# Sheet5.net
KiCad netlist of a schematic drawn in Altium Designer
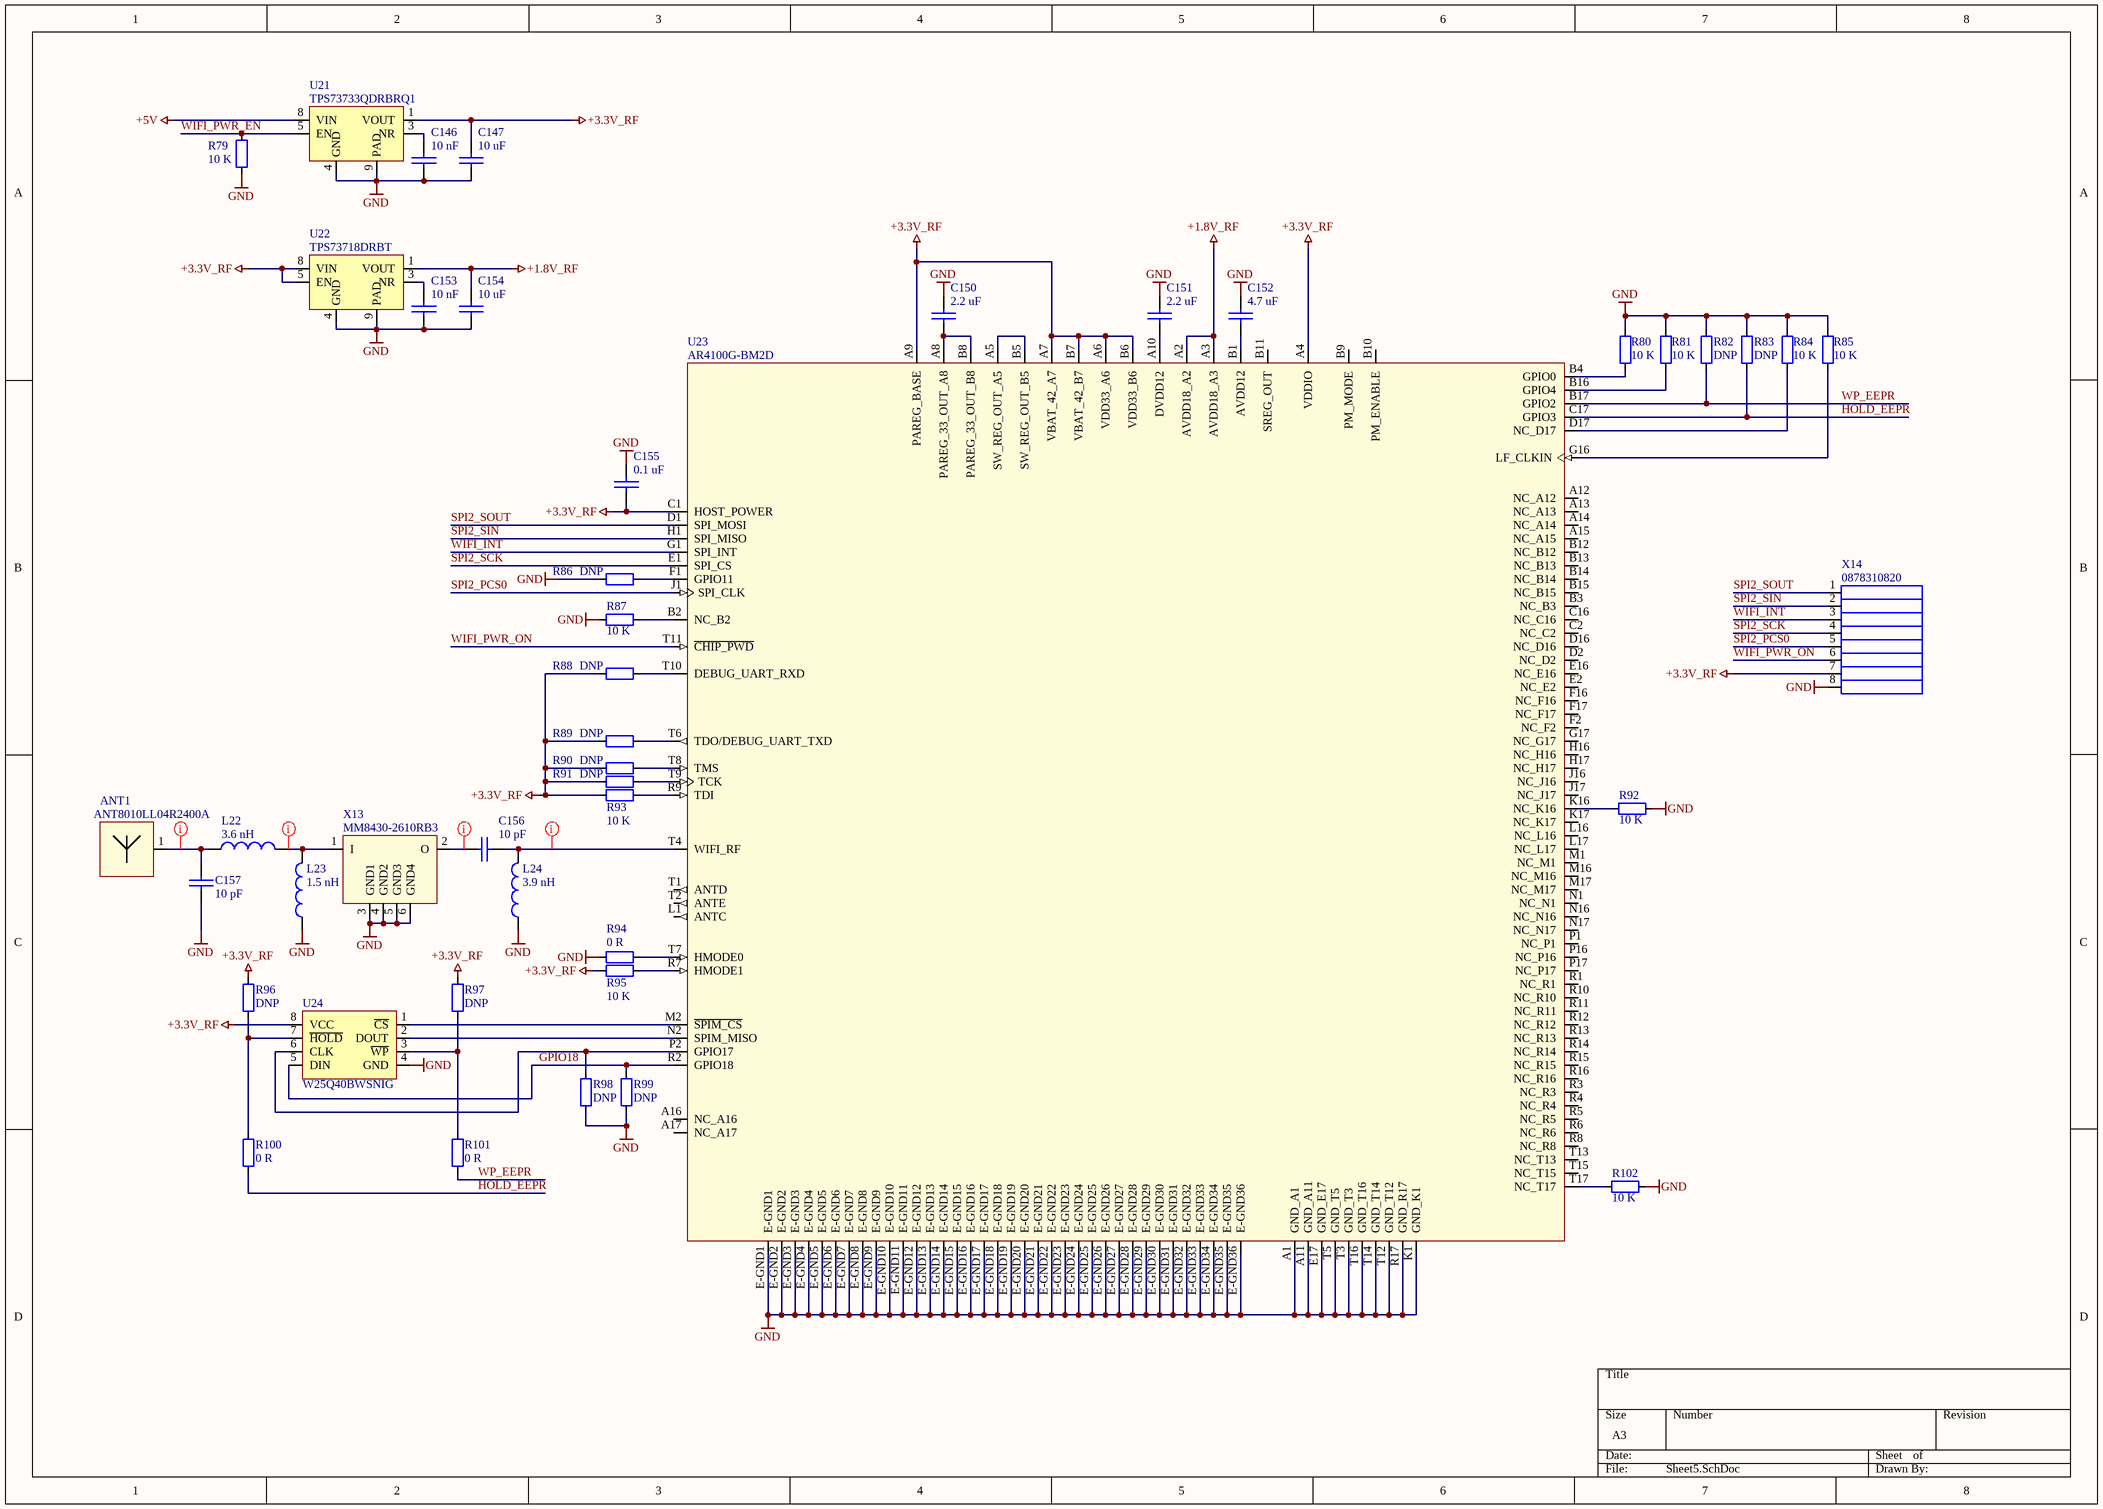
[diagram p0: Sheet5.SchDoc]

(export (version "E")
  (design (tool "Eeschema 10.0.6"))
  (components
    (comp (ref "ANT1")
      (value "ANT8010LL04R2400A")
      (footprint "ANT8010LL04R2400A")
      (description "Chip ant. 2.4GHz ~ 2.5GHz, 5.5dBi")
      (fields (field (name "MANUFACTURER") "Yageo") (field (name "PARTNUM") "311-1550-1-ND"))
      (libsource (lib "ea_IC_RF") (part "ANT8010LL04R2400A"))
    )
    (comp (ref "C146")
      (value "10 nF")
      (footprint "1005[0402]")
      (description "10 nF, 16V, 10%, X7R, 0402")
      (fields (field (name "TOLERANCE") "10%") (field (name "MANUFACTURER") "SAMSUNG"))
      (libsource (lib "ea_Capacitors") (part "GRM155R71C103KA01D_1"))
    )
    (comp (ref "C147")
      (value "10 uF")
      (footprint "2012[0805]")
      (description "10 uF, 16V, X5R, ±10%, 0805")
      (fields (field (name "MANUFACTURER") "TDK Corporation") (field (name "TOLERANCE") "±10%"))
      (libsource (lib "ea_Capacitors") (part "C2012X5R1C106K/0.85"))
    )
    (comp (ref "C150")
      (value "2.2 uF")
      (footprint "1005[0402]")
      (description "2.2 uF, 6.3V, 20%, X5R, -55..85C, 0402")
      (fields (field (name "TOLERANCE") "20%") (field (name "MANUFACTURER") "SAMSUNG"))
      (libsource (lib "ea_Capacitors") (part "C0402C225M9PACTU"))
    )
    (comp (ref "C151")
      (value "2.2 uF")
      (footprint "1005[0402]")
      (description "2.2 uF, 6.3V, 20%, X5R, -55..85C, 0402")
      (fields (field (name "TOLERANCE") "20%") (field (name "MANUFACTURER") "SAMSUNG"))
      (libsource (lib "ea_Capacitors") (part "C0402C225M9PACTU"))
    )
    (comp (ref "C152")
      (value "4.7 uF")
      (footprint "1608[0603]")
      (description "4.7 uF, 10V, 10%, X5R, 0603")
      (fields (field (name "TOLERANCE") "+-10%") (field (name "MANUFACTURER") "Taiyo Yuden"))
      (libsource (lib "ea_Capacitors") (part "LMK107BJ475KA-T"))
    )
    (comp (ref "C153")
      (value "10 nF")
      (footprint "1005[0402]")
      (description "10 nF, 16V, 10%, X7R, 0402")
      (fields (field (name "TOLERANCE") "10%") (field (name "MANUFACTURER") "SAMSUNG"))
      (libsource (lib "ea_Capacitors") (part "GRM155R71C103KA01D_1"))
    )
    (comp (ref "C154")
      (value "10 uF")
      (footprint "2012[0805]")
      (description "10 uF, 16V, X5R, ±10%, 0805")
      (fields (field (name "TOLERANCE") "±10%") (field (name "MANUFACTURER") "TDK Corporation"))
      (libsource (lib "ea_Capacitors") (part "C2012X5R1C106K/0.85"))
    )
    (comp (ref "C155")
      (value "0.1 uF")
      (footprint "1005[0402]")
      (description "0.1 uF, 16V, 10%, X7R, 0402")
      (fields (field (name "TOLERANCE") "10%") (field (name "MANUFACTURER") "SAMSUNG"))
      (libsource (lib "ea_Capacitors") (part "GRM155R71C104KA88D_1"))
    )
    (comp (ref "C156")
      (value "10 pF")
      (footprint "1005[0402]")
      (description "10 pF, 50V, 5%, NP0/COG, 0402")
      (fields (field (name "MANUFACTURER") "Murata") (field (name "TOLERANCE") "5%"))
      (libsource (lib "ea_Capacitors") (part "GRM1555C1H100JZ01D"))
    )
    (comp (ref "C157")
      (value "10 pF")
      (footprint "1005[0402]")
      (description "10 pF, 50V, 5%, NP0/COG, 0402")
      (fields (field (name "MANUFACTURER") "Murata") (field (name "TOLERANCE") "5%"))
      (libsource (lib "ea_Capacitors") (part "GRM1555C1H100JZ01D"))
    )
    (comp (ref "L22")
      (value "3.6 nH")
      (footprint "INDC1005-0402")
      (description "3.6 nH, ±0.1nH, 170 мА, 0402")
      (fields (field (name "MANUFACTURER") "Murata") (field (name "TOLERANCE") "±0.1nH"))
      (libsource (lib "ea_Inductors") (part "LQP15MN3N6B02D"))
    )
    (comp (ref "L23")
      (value "1.5 nH")
      (footprint "INDC1005-0402")
      (description "1.5 nH, ±0.1nH, 280 мА, 0402")
      (fields (field (name "MANUFACTURER") "Murata") (field (name "TOLERANCE") "±0.1nH"))
      (libsource (lib "ea_Inductors") (part "LQP15MN1N5B02D"))
    )
    (comp (ref "L24")
      (value "3.9 nH")
      (footprint "INDC1005-0402")
      (description "3.9 nH, ±0.1nH, 170 мА, 0402")
      (fields (field (name "MANUFACTURER") "Murata") (field (name "TOLERANCE") "±0.1nH"))
      (libsource (lib "ea_Inductors") (part "LQP15MN3N9B02D"))
    )
    (comp (ref "R79")
      (value "10 K")
      (footprint "0603")
      (description "10 K, 1%, 0603, SMD Resistor, Taped")
      (fields (field (name "MANUFACTURER") "PANASONIC") (field (name "TOLERANCE") "1%"))
      (libsource (lib "ea_Resistors") (part "RL0603K010-1"))
    )
    (comp (ref "R80")
      (value "10 K")
      (footprint "0402")
      (description "10 K, 5%, 0402, SMD Resistor, Taped")
      (fields (field (name "MANUFACTURER") "Yageo") (field (name "TOLERANCE") "5%"))
      (libsource (lib "") (part "RC0402JR-0710KL_1"))
    )
    (comp (ref "R81")
      (value "10 K")
      (footprint "0402")
      (description "10 K, 5%, 0402, SMD Resistor, Taped")
      (fields (field (name "MANUFACTURER") "Yageo") (field (name "TOLERANCE") "5%"))
      (libsource (lib "") (part "RC0402JR-0710KL_1"))
    )
    (comp (ref "R82")
      (value "DNP")
      (footprint "0603")
      (description "DNP, 0603")
      (fields (field (name "Comment") "DNP_0603"))
      (libsource (lib "ea_Resistors") (part "DNP_0603"))
    )
    (comp (ref "R83")
      (value "DNP")
      (footprint "0603")
      (description "DNP, 0603")
      (fields (field (name "Comment") "DNP_0603"))
      (libsource (lib "ea_Resistors") (part "DNP_0603"))
    )
    (comp (ref "R84")
      (value "10 K")
      (footprint "0402")
      (description "10 K, 5%, 0402, SMD Resistor, Taped")
      (fields (field (name "MANUFACTURER") "Yageo") (field (name "TOLERANCE") "5%"))
      (libsource (lib "") (part "RC0402JR-0710KL_1"))
    )
    (comp (ref "R85")
      (value "10 K")
      (footprint "0402")
      (description "10 K, 5%, 0402, SMD Resistor, Taped")
      (fields (field (name "MANUFACTURER") "Yageo") (field (name "TOLERANCE") "5%"))
      (libsource (lib "") (part "RC0402JR-0710KL_1"))
    )
    (comp (ref "R86")
      (value "DNP")
      (footprint "0603")
      (description "DNP, 0603")
      (fields (field (name "Comment") "DNP_0603"))
      (libsource (lib "") (part "DNP_0603_1"))
    )
    (comp (ref "R87")
      (value "10 K")
      (footprint "0402")
      (description "10 K, 5%, 0402, SMD Resistor, Taped")
      (fields (field (name "MANUFACTURER") "Yageo") (field (name "TOLERANCE") "5%"))
      (libsource (lib "ea_Resistors") (part "RC0402JR-0710KL"))
    )
    (comp (ref "R88")
      (value "DNP")
      (footprint "0603")
      (description "DNP, 0603")
      (fields (field (name "Comment") "DNP_0603"))
      (libsource (lib "") (part "DNP_0603_1"))
    )
    (comp (ref "R89")
      (value "DNP")
      (footprint "0603")
      (description "DNP, 0603")
      (fields (field (name "Comment") "DNP_0603"))
      (libsource (lib "") (part "DNP_0603_1"))
    )
    (comp (ref "R90")
      (value "DNP")
      (footprint "0603")
      (description "DNP, 0603")
      (fields (field (name "Comment") "DNP_0603"))
      (libsource (lib "") (part "DNP_0603_1"))
    )
    (comp (ref "R91")
      (value "DNP")
      (footprint "0603")
      (description "DNP, 0603")
      (fields (field (name "Comment") "DNP_0603"))
      (libsource (lib "") (part "DNP_0603_1"))
    )
    (comp (ref "R92")
      (value "10 K")
      (footprint "0402")
      (description "10 K, 5%, 0402, SMD Resistor, Taped")
      (fields (field (name "MANUFACTURER") "Yageo") (field (name "TOLERANCE") "5%"))
      (libsource (lib "ea_Resistors") (part "RC0402JR-0710KL"))
    )
    (comp (ref "R93")
      (value "10 K")
      (footprint "0402")
      (description "10 K, 5%, 0402, SMD Resistor, Taped")
      (fields (field (name "MANUFACTURER") "Yageo") (field (name "TOLERANCE") "5%"))
      (libsource (lib "ea_Resistors") (part "RC0402JR-0710KL"))
    )
    (comp (ref "R94")
      (value "0 R")
      (footprint "0603")
      (description "0 R, 5%, 0603, SMD Resistor, Taped")
      (fields (field (name "MANUFACTURER") "YAGEO AMERICA CORPORATION") (field (name "TOLERANCE") "5%"))
      (libsource (lib "ea_Resistors") (part "RL0603E000"))
    )
    (comp (ref "R95")
      (value "10 K")
      (footprint "0402")
      (description "10 K, 5%, 0402, SMD Resistor, Taped")
      (fields (field (name "MANUFACTURER") "Yageo") (field (name "TOLERANCE") "5%"))
      (libsource (lib "ea_Resistors") (part "RC0402JR-0710KL"))
    )
    (comp (ref "R96")
      (value "DNP")
      (footprint "0603")
      (description "DNP, 0603")
      (fields (field (name "Comment") "DNP_0603"))
      (libsource (lib "ea_Resistors") (part "DNP_0603"))
    )
    (comp (ref "R97")
      (value "DNP")
      (footprint "0603")
      (description "DNP, 0603")
      (fields (field (name "Comment") "DNP_0603"))
      (libsource (lib "ea_Resistors") (part "DNP_0603"))
    )
    (comp (ref "R98")
      (value "DNP")
      (footprint "0603")
      (description "DNP, 0603")
      (fields (field (name "Comment") "DNP_0603"))
      (libsource (lib "ea_Resistors") (part "DNP_0603"))
    )
    (comp (ref "R99")
      (value "DNP")
      (footprint "0603")
      (description "DNP, 0603")
      (fields (field (name "Comment") "DNP_0603"))
      (libsource (lib "ea_Resistors") (part "DNP_0603"))
    )
    (comp (ref "R100")
      (value "0 R")
      (footprint "0603")
      (description "0 R, 5%, 0603, SMD Resistor, Taped")
      (fields (field (name "MANUFACTURER") "YAGEO AMERICA CORPORATION") (field (name "TOLERANCE") "5%"))
      (libsource (lib "") (part "RL0603E000_1"))
    )
    (comp (ref "R101")
      (value "0 R")
      (footprint "0603")
      (description "0 R, 5%, 0603, SMD Resistor, Taped")
      (fields (field (name "MANUFACTURER") "YAGEO AMERICA CORPORATION") (field (name "TOLERANCE") "5%"))
      (libsource (lib "") (part "RL0603E000_1"))
    )
    (comp (ref "R102")
      (value "10 K")
      (footprint "0402")
      (description "10 K, 5%, 0402, SMD Resistor, Taped")
      (fields (field (name "MANUFACTURER") "Yageo") (field (name "TOLERANCE") "5%"))
      (libsource (lib "ea_Resistors") (part "RC0402JR-0710KL"))
    )
    (comp (ref "U21")
      (value "TPS73733QDRBRQ1")
      (footprint "TI DRB (S-PVSON-N8)")
      (description "LDO 3.3V 1A , up to 5.5 V, -40..125C,  8-SON")
      (fields (field (name "MANUFACTURER") "Texas Instruments") (field (name "PARTNUM") "296-24157-1-ND"))
      (libsource (lib "ea_IC_Power_Reg_Ref_Sw") (part "TPS73733QDRBRQ1"))
    )
    (comp (ref "U22")
      (value "TPS73718DRBT")
      (footprint "TI DRB (S-PVSON-N8)")
      (description "LDO 1.8V 1A , 2.2..5.5 V, -40..125C,  8-SON")
      (fields (field (name "MANUFACTURER") "Texas Instruments") (field (name "PARTNUM") "296-28932-1-ND"))
      (libsource (lib "ea_IC_Power_Reg_Ref_Sw") (part "TPS73718DRBT"))
    )
    (comp (ref "U23")
      (value "AR4100G-BM2D")
      (footprint "AR4100 BGA147")
      (description "Atheros single-stream 802.11n system-in-package Wi-Fi-System")
      (fields (field (name "MANUFACTURER") "Qualcomm"))
      (libsource (lib "ea_IC_RF") (part "AR4100G-BM2D"))
    )
    (comp (ref "U24")
      (value "W25Q40BWSNIG")
      (footprint "SO-8")
      (description "FLASH 4MBIT 80MHZ,  1.65..1.95V, -40..85C, 8SOIC")
      (fields (field (name "MANUFACTURER") "Winbond Electronics") (field (name "PARTNUM") "W25Q40BWSNIG-ND"))
      (libsource (lib "ea_IC_NOR_NAND_FLASH") (part "W25Q40BWSNIG"))
    )
    (comp (ref "X13")
      (value "MM8430-2610RB3")
      (footprint "MM8430-2610RB3")
      (description "ONN SWD JACK STR 50 OHM SMD")
      (fields
        (field (name "MANUFACTURER") "Murata Electronics North America")
        (field (name "PARTNUM") "490-8451-6-ND")
      )
      (libsource (lib "ea_IC_RF") (part "MM8430-2610RB3"))
    )
    (comp (ref "X14")
      (value "0878310820")
      (footprint "0878310820 MGRID WALL HDR SMD")
      (description "CONN HEADER 8POS 2MM VERT GOLD")
      (fields (field (name "MANUFACTURER") "Molex Inc") (field (name "PARTNUM") "WM18559-ND"))
      (libsource (lib "ea_Connectors") (part "0878310820"))
    )
  )
  (nets
    (net (code "1") (name "+1.8V_RF") (class "Default")
      (node (ref "C154") (pin "1") (pinfunction "1_1") (pintype "passive"))
      (node (ref "U22") (pin "1") (pinfunction "VOUT_1") (pintype "passive"))
      (node (ref "U23") (pin "A2") (pinfunction "AVDD18_A2_A2") (pintype "power_in"))
      (node (ref "U23") (pin "A3") (pinfunction "AVDD18_A3_A3") (pintype "power_in"))
    )
    (net (code "2") (name "+3.3V_RF") (class "Default")
      (node (ref "C147") (pin "2") (pinfunction "2_2") (pintype "passive"))
      (node (ref "C155") (pin "2") (pinfunction "2_2") (pintype "passive"))
      (node (ref "R88") (pin "2") (pinfunction "2_2") (pintype "passive"))
      (node (ref "R89") (pin "2") (pinfunction "2_2") (pintype "passive"))
      (node (ref "R90") (pin "2") (pinfunction "2_2") (pintype "passive"))
      (node (ref "R91") (pin "2") (pinfunction "2_2") (pintype "passive"))
      (node (ref "R93") (pin "2") (pinfunction "2_2") (pintype "passive"))
      (node (ref "R95") (pin "2") (pinfunction "2_2") (pintype "passive"))
      (node (ref "R96") (pin "2") (pinfunction "2_2") (pintype "passive"))
      (node (ref "R97") (pin "2") (pinfunction "2_2") (pintype "passive"))
      (node (ref "U21") (pin "1") (pinfunction "VOUT_1") (pintype "passive"))
      (node (ref "U22") (pin "5") (pinfunction "EN_5") (pintype "power_in"))
      (node (ref "U22") (pin "8") (pinfunction "VIN_8") (pintype "power_in"))
      (node (ref "U23") (pin "A4") (pinfunction "VDDIO_A4") (pintype "power_in"))
      (node (ref "U23") (pin "A6") (pinfunction "VDD33_A6_A6") (pintype "power_in"))
      (node (ref "U23") (pin "A7") (pinfunction "VBAT_42_A7_A7") (pintype "power_in"))
      (node (ref "U23") (pin "A9") (pinfunction "PAREG_BASE_A9") (pintype "power_in"))
      (node (ref "U23") (pin "B6") (pinfunction "VDD33_B6_B6") (pintype "power_in"))
      (node (ref "U23") (pin "B7") (pinfunction "VBAT_42_B7_B7") (pintype "power_in"))
      (node (ref "U23") (pin "C1") (pinfunction "HOST_POWER_C1") (pintype "power_in"))
      (node (ref "U24") (pin "8") (pinfunction "VCC_8") (pintype "passive"))
      (node (ref "X14") (pin "7") (pinfunction "7_7") (pintype "passive"))
    )
    (net (code "3") (name "+5V") (class "Default")
      (node (ref "U21") (pin "8") (pinfunction "VIN_8") (pintype "power_in"))
    )
    (net (code "4") (name "/GPIO18") (class "Default")
      (node (ref "R99") (pin "2") (pinfunction "2_2") (pintype "passive"))
      (node (ref "U23") (pin "R2") (pinfunction "GPIO18_R2") (pintype "bidirectional"))
      (node (ref "U24") (pin "5") (pinfunction "DIN_5") (pintype "passive"))
    )
    (net (code "5") (name "/HOLD_EEPR") (class "Default")
      (node (ref "R100") (pin "2") (pinfunction "2_2") (pintype "passive"))
      (node (ref "R83") (pin "1") (pinfunction "1_1") (pintype "passive"))
      (node (ref "U23") (pin "C17") (pinfunction "GPIO3_C17") (pintype "bidirectional"))
    )
    (net (code "6") (name "/SPI2_PCS0") (class "Default")
      (node (ref "U23") (pin "J1") (pinfunction "SPI_CLK_J1") (pintype "input"))
      (node (ref "X14") (pin "5") (pinfunction "5_5") (pintype "passive"))
    )
    (net (code "7") (name "/SPI2_SCK") (class "Default")
      (node (ref "U23") (pin "E1") (pinfunction "SPI_CS_E1") (pintype "bidirectional"))
      (node (ref "X14") (pin "4") (pinfunction "4_4") (pintype "passive"))
    )
    (net (code "8") (name "/SPI2_SIN") (class "Default")
      (node (ref "U23") (pin "H1") (pinfunction "SPI_MISO_H1") (pintype "bidirectional"))
      (node (ref "X14") (pin "2") (pinfunction "2_2") (pintype "passive"))
    )
    (net (code "9") (name "/SPI2_SOUT") (class "Default")
      (node (ref "U23") (pin "D1") (pinfunction "SPI_MOSI_D1") (pintype "bidirectional"))
      (node (ref "X14") (pin "1") (pinfunction "1_1") (pintype "power_in"))
    )
    (net (code "10") (name "/WIFI_INT") (class "Default")
      (node (ref "U23") (pin "G1") (pinfunction "SPI_INT_G1") (pintype "bidirectional"))
      (node (ref "X14") (pin "3") (pinfunction "3_3") (pintype "passive"))
    )
    (net (code "11") (name "/WIFI_PWR_EN") (class "Default")
      (node (ref "R79") (pin "1") (pinfunction "1_1") (pintype "passive"))
      (node (ref "U21") (pin "5") (pinfunction "EN_5") (pintype "power_in"))
    )
    (net (code "12") (name "/WIFI_PWR_ON") (class "Default")
      (node (ref "U23") (pin "T11") (pinfunction "~{CHIP_PWD}_T11") (pintype "input"))
      (node (ref "X14") (pin "6") (pinfunction "6_6") (pintype "passive"))
    )
    (net (code "13") (name "/WP_EEPR") (class "Default")
      (node (ref "R101") (pin "2") (pinfunction "2_2") (pintype "passive"))
      (node (ref "R82") (pin "1") (pinfunction "1_1") (pintype "passive"))
      (node (ref "U23") (pin "B17") (pinfunction "GPIO2_B17") (pintype "bidirectional"))
    )
    (net (code "14") (name "GND") (class "Default")
      (node (ref "C146") (pin "2") (pinfunction "2_2") (pintype "passive"))
      (node (ref "C147") (pin "1") (pinfunction "1_1") (pintype "passive"))
      (node (ref "C150") (pin "1") (pinfunction "1_1") (pintype "passive"))
      (node (ref "C151") (pin "1") (pinfunction "1_1") (pintype "passive"))
      (node (ref "C152") (pin "1") (pinfunction "1_1") (pintype "passive"))
      (node (ref "C153") (pin "2") (pinfunction "2_2") (pintype "passive"))
      (node (ref "C154") (pin "2") (pinfunction "2_2") (pintype "passive"))
      (node (ref "C155") (pin "1") (pinfunction "1_1") (pintype "passive"))
      (node (ref "C157") (pin "1") (pinfunction "1_1") (pintype "passive"))
      (node (ref "L23") (pin "1") (pinfunction "1_1") (pintype "passive"))
      (node (ref "L24") (pin "1") (pinfunction "1_1") (pintype "passive"))
      (node (ref "R102") (pin "1") (pinfunction "1_1") (pintype "passive"))
      (node (ref "R79") (pin "2") (pinfunction "2_2") (pintype "passive"))
      (node (ref "R80") (pin "2") (pinfunction "2_2") (pintype "passive"))
      (node (ref "R81") (pin "2") (pinfunction "2_2") (pintype "passive"))
      (node (ref "R82") (pin "2") (pinfunction "2_2") (pintype "passive"))
      (node (ref "R83") (pin "2") (pinfunction "2_2") (pintype "passive"))
      (node (ref "R84") (pin "2") (pinfunction "2_2") (pintype "passive"))
      (node (ref "R85") (pin "2") (pinfunction "2_2") (pintype "passive"))
      (node (ref "R86") (pin "2") (pinfunction "2_2") (pintype "passive"))
      (node (ref "R87") (pin "2") (pinfunction "2_2") (pintype "passive"))
      (node (ref "R92") (pin "1") (pinfunction "1_1") (pintype "passive"))
      (node (ref "R94") (pin "2") (pinfunction "2_2") (pintype "passive"))
      (node (ref "R98") (pin "1") (pinfunction "1_1") (pintype "passive"))
      (node (ref "R99") (pin "1") (pinfunction "1_1") (pintype "passive"))
      (node (ref "U21") (pin "4") (pinfunction "GND_4") (pintype "power_in"))
      (node (ref "U21") (pin "9") (pinfunction "PAD_9") (pintype "passive"))
      (node (ref "U22") (pin "4") (pinfunction "GND_4") (pintype "power_in"))
      (node (ref "U22") (pin "9") (pinfunction "PAD_9") (pintype "passive"))
      (node (ref "U23") (pin "A1") (pinfunction "GND_A1_A1") (pintype "power_in"))
      (node (ref "U23") (pin "A11") (pinfunction "GND_A11_A11") (pintype "power_in"))
      (node (ref "U23") (pin "E-GND1") (pinfunction "E-GND1_E-GND1") (pintype "power_in"))
      (node (ref "U23") (pin "E-GND10") (pinfunction "E-GND10_E-GND10") (pintype "power_in"))
      (node (ref "U23") (pin "E-GND11") (pinfunction "E-GND11_E-GND11") (pintype "power_in"))
      (node (ref "U23") (pin "E-GND12") (pinfunction "E-GND12_E-GND12") (pintype "power_in"))
      (node (ref "U23") (pin "E-GND13") (pinfunction "E-GND13_E-GND13") (pintype "power_in"))
      (node (ref "U23") (pin "E-GND14") (pinfunction "E-GND14_E-GND14") (pintype "power_in"))
      (node (ref "U23") (pin "E-GND15") (pinfunction "E-GND15_E-GND15") (pintype "power_in"))
      (node (ref "U23") (pin "E-GND16") (pinfunction "E-GND16_E-GND16") (pintype "power_in"))
      (node (ref "U23") (pin "E-GND17") (pinfunction "E-GND17_E-GND17") (pintype "power_in"))
      (node (ref "U23") (pin "E-GND18") (pinfunction "E-GND18_E-GND18") (pintype "power_in"))
      (node (ref "U23") (pin "E-GND19") (pinfunction "E-GND19_E-GND19") (pintype "power_in"))
      (node (ref "U23") (pin "E-GND2") (pinfunction "E-GND2_E-GND2") (pintype "power_in"))
      (node (ref "U23") (pin "E-GND20") (pinfunction "E-GND20_E-GND20") (pintype "power_in"))
      (node (ref "U23") (pin "E-GND21") (pinfunction "E-GND21_E-GND21") (pintype "power_in"))
      (node (ref "U23") (pin "E-GND22") (pinfunction "E-GND22_E-GND22") (pintype "power_in"))
      (node (ref "U23") (pin "E-GND23") (pinfunction "E-GND23_E-GND23") (pintype "power_in"))
      (node (ref "U23") (pin "E-GND24") (pinfunction "E-GND24_E-GND24") (pintype "power_in"))
      (node (ref "U23") (pin "E-GND25") (pinfunction "E-GND25_E-GND25") (pintype "power_in"))
      (node (ref "U23") (pin "E-GND26") (pinfunction "E-GND26_E-GND26") (pintype "power_in"))
      (node (ref "U23") (pin "E-GND27") (pinfunction "E-GND27_E-GND27") (pintype "power_in"))
      (node (ref "U23") (pin "E-GND28") (pinfunction "E-GND28_E-GND28") (pintype "power_in"))
      (node (ref "U23") (pin "E-GND29") (pinfunction "E-GND29_E-GND29") (pintype "power_in"))
      (node (ref "U23") (pin "E-GND3") (pinfunction "E-GND3_E-GND3") (pintype "power_in"))
      (node (ref "U23") (pin "E-GND30") (pinfunction "E-GND30_E-GND30") (pintype "power_in"))
      (node (ref "U23") (pin "E-GND31") (pinfunction "E-GND31_E-GND31") (pintype "power_in"))
      (node (ref "U23") (pin "E-GND32") (pinfunction "E-GND32_E-GND32") (pintype "power_in"))
      (node (ref "U23") (pin "E-GND33") (pinfunction "E-GND33_E-GND33") (pintype "power_in"))
      (node (ref "U23") (pin "E-GND34") (pinfunction "E-GND34_E-GND34") (pintype "power_in"))
      (node (ref "U23") (pin "E-GND35") (pinfunction "E-GND35_E-GND35") (pintype "power_in"))
      (node (ref "U23") (pin "E-GND36") (pinfunction "E-GND36_E-GND36") (pintype "power_in"))
      (node (ref "U23") (pin "E-GND4") (pinfunction "E-GND4_E-GND4") (pintype "power_in"))
      (node (ref "U23") (pin "E-GND5") (pinfunction "E-GND5_E-GND5") (pintype "power_in"))
      (node (ref "U23") (pin "E-GND6") (pinfunction "E-GND6_E-GND6") (pintype "power_in"))
      (node (ref "U23") (pin "E-GND7") (pinfunction "E-GND7_E-GND7") (pintype "power_in"))
      (node (ref "U23") (pin "E-GND8") (pinfunction "E-GND8_E-GND8") (pintype "power_in"))
      (node (ref "U23") (pin "E-GND9") (pinfunction "E-GND9_E-GND9") (pintype "power_in"))
      (node (ref "U23") (pin "E17") (pinfunction "GND_E17_E17") (pintype "power_in"))
      (node (ref "U23") (pin "K1") (pinfunction "GND_K1_K1") (pintype "power_in"))
      (node (ref "U23") (pin "R17") (pinfunction "GND_R17_R17") (pintype "power_in"))
      (node (ref "U23") (pin "T12") (pinfunction "GND_T12_T12") (pintype "power_in"))
      (node (ref "U23") (pin "T14") (pinfunction "GND_T14_T14") (pintype "power_in"))
      (node (ref "U23") (pin "T16") (pinfunction "GND_T16_T16") (pintype "power_in"))
      (node (ref "U23") (pin "T3") (pinfunction "GND_T3_T3") (pintype "power_in"))
      (node (ref "U23") (pin "T5") (pinfunction "GND_T5_T5") (pintype "power_in"))
      (node (ref "U24") (pin "4") (pinfunction "GND_4") (pintype "passive"))
      (node (ref "X13") (pin "3") (pinfunction "GND1_3") (pintype "power_in"))
      (node (ref "X13") (pin "4") (pinfunction "GND2_4") (pintype "power_in"))
      (node (ref "X13") (pin "5") (pinfunction "GND3_5") (pintype "power_in"))
      (node (ref "X13") (pin "6") (pinfunction "GND4_6") (pintype "power_in"))
      (node (ref "X14") (pin "8") (pinfunction "8_8") (pintype "passive"))
    )
    (net (code "15") (name "Net-(ANT1-INPUT)") (class "Default")
      (node (ref "ANT1") (pin "1") (pinfunction "INPUT_1") (pintype "passive"))
      (node (ref "C157") (pin "2") (pinfunction "2_2") (pintype "passive"))
      (node (ref "L22") (pin "1") (pinfunction "1_1") (pintype "passive"))
    )
    (net (code "16") (name "Net-(U21-NR)") (class "Default")
      (node (ref "C146") (pin "1") (pinfunction "1_1") (pintype "passive"))
      (node (ref "U21") (pin "3") (pinfunction "NR_3") (pintype "passive"))
    )
    (net (code "17") (name "Net-(U22-NR)") (class "Default")
      (node (ref "C153") (pin "1") (pinfunction "1_1") (pintype "passive"))
      (node (ref "U22") (pin "3") (pinfunction "NR_3") (pintype "passive"))
    )
    (net (code "18") (name "Net-(U23-AVDD12)") (class "Default")
      (node (ref "C152") (pin "2") (pinfunction "2_2") (pintype "passive"))
      (node (ref "U23") (pin "B1") (pinfunction "AVDD12_B1") (pintype "power_in"))
    )
    (net (code "19") (name "Net-(U23-DEBUG_UART_RXD)") (class "Default")
      (node (ref "R88") (pin "1") (pinfunction "1_1") (pintype "passive"))
      (node (ref "U23") (pin "T10") (pinfunction "DEBUG_UART_RXD_T10") (pintype "passive"))
    )
    (net (code "20") (name "Net-(U23-DVDD12)") (class "Default")
      (node (ref "C151") (pin "2") (pinfunction "2_2") (pintype "passive"))
      (node (ref "U23") (pin "A10") (pinfunction "DVDD12_A10") (pintype "power_in"))
    )
    (net (code "21") (name "Net-(U23-GPIO0)") (class "Default")
      (node (ref "R80") (pin "1") (pinfunction "1_1") (pintype "passive"))
      (node (ref "U23") (pin "B4") (pinfunction "GPIO0_B4") (pintype "bidirectional"))
    )
    (net (code "22") (name "Net-(U23-GPIO4)") (class "Default")
      (node (ref "R81") (pin "1") (pinfunction "1_1") (pintype "passive"))
      (node (ref "U23") (pin "B16") (pinfunction "GPIO4_B16") (pintype "bidirectional"))
    )
    (net (code "23") (name "Net-(U23-GPIO11)") (class "Default")
      (node (ref "R86") (pin "1") (pinfunction "1_1") (pintype "passive"))
      (node (ref "U23") (pin "F1") (pinfunction "GPIO11_F1") (pintype "bidirectional"))
    )
    (net (code "24") (name "Net-(U23-GPIO17)") (class "Default")
      (node (ref "R98") (pin "2") (pinfunction "2_2") (pintype "passive"))
      (node (ref "U23") (pin "P2") (pinfunction "GPIO17_P2") (pintype "bidirectional"))
      (node (ref "U24") (pin "6") (pinfunction "CLK_6") (pintype "passive"))
    )
    (net (code "25") (name "Net-(U23-HMODE0)") (class "Default")
      (node (ref "R94") (pin "1") (pinfunction "1_1") (pintype "passive"))
      (node (ref "U23") (pin "T7") (pinfunction "HMODE0_T7") (pintype "input"))
    )
    (net (code "26") (name "Net-(U23-HMODE1)") (class "Default")
      (node (ref "R95") (pin "1") (pinfunction "1_1") (pintype "passive"))
      (node (ref "U23") (pin "R7") (pinfunction "HMODE1_R7") (pintype "input"))
    )
    (net (code "27") (name "Net-(U23-LF_CLKIN)") (class "Default")
      (node (ref "R85") (pin "1") (pinfunction "1_1") (pintype "passive"))
      (node (ref "U23") (pin "G16") (pinfunction "LF_CLKIN_G16") (pintype "input"))
    )
    (net (code "28") (name "Net-(U23-NC_B2)") (class "Default")
      (node (ref "R87") (pin "1") (pinfunction "1_1") (pintype "passive"))
      (node (ref "U23") (pin "B2") (pinfunction "NC_B2_B2") (pintype "passive"))
    )
    (net (code "29") (name "Net-(U23-NC_D17)") (class "Default")
      (node (ref "R84") (pin "1") (pinfunction "1_1") (pintype "passive"))
      (node (ref "U23") (pin "D17") (pinfunction "NC_D17_D17") (pintype "passive"))
    )
    (net (code "30") (name "Net-(U23-NC_K16)") (class "Default")
      (node (ref "R92") (pin "2") (pinfunction "2_2") (pintype "passive"))
      (node (ref "U23") (pin "K16") (pinfunction "NC_K16_K16") (pintype "passive"))
    )
    (net (code "31") (name "Net-(U23-NC_T17)") (class "Default")
      (node (ref "R102") (pin "2") (pinfunction "2_2") (pintype "passive"))
      (node (ref "U23") (pin "T17") (pinfunction "NC_T17_T17") (pintype "passive"))
    )
    (net (code "32") (name "Net-(U23-PAREG_33_OUT_A8)") (class "Default")
      (node (ref "C150") (pin "2") (pinfunction "2_2") (pintype "passive"))
      (node (ref "U23") (pin "A8") (pinfunction "PAREG_33_OUT_A8_A8") (pintype "power_in"))
      (node (ref "U23") (pin "B8") (pinfunction "PAREG_33_OUT_B8_B8") (pintype "power_in"))
    )
    (net (code "33") (name "Net-(U23-SPIM_MISO)") (class "Default")
      (node (ref "U23") (pin "N2") (pinfunction "SPIM_MISO_N2") (pintype "bidirectional"))
      (node (ref "U24") (pin "2") (pinfunction "DOUT_2") (pintype "passive"))
    )
    (net (code "34") (name "Net-(U23-SW_REG_OUT_A5)") (class "Default")
      (node (ref "U23") (pin "A5") (pinfunction "SW_REG_OUT_A5_A5") (pintype "power_in"))
      (node (ref "U23") (pin "B5") (pinfunction "SW_REG_OUT_B5_B5") (pintype "power_in"))
    )
    (net (code "35") (name "Net-(U23-TCK)") (class "Default")
      (node (ref "R91") (pin "1") (pinfunction "1_1") (pintype "passive"))
      (node (ref "U23") (pin "T9") (pinfunction "TCK_T9") (pintype "input"))
    )
    (net (code "36") (name "Net-(U23-TDI)") (class "Default")
      (node (ref "R93") (pin "1") (pinfunction "1_1") (pintype "passive"))
      (node (ref "U23") (pin "R9") (pinfunction "TDI_R9") (pintype "input"))
    )
    (net (code "37") (name "Net-(U23-TDO{slash}DEBUG_UART_TXD)") (class "Default")
      (node (ref "R89") (pin "1") (pinfunction "1_1") (pintype "passive"))
      (node (ref "U23") (pin "T6") (pinfunction "TDO/DEBUG_UART_TXD_T6") (pintype "output"))
    )
    (net (code "38") (name "Net-(U23-TMS)") (class "Default")
      (node (ref "R90") (pin "1") (pinfunction "1_1") (pintype "passive"))
      (node (ref "U23") (pin "T8") (pinfunction "TMS_T8") (pintype "input"))
    )
    (net (code "39") (name "Net-(U23-WIFI_RF)") (class "Default")
      (node (ref "C156") (pin "2") (pinfunction "2_2") (pintype "passive"))
      (node (ref "L24") (pin "2") (pinfunction "2_2") (pintype "passive"))
      (node (ref "U23") (pin "T4") (pinfunction "WIFI_RF_T4") (pintype "bidirectional"))
    )
    (net (code "40") (name "Net-(U23-~{SPIM_CS})") (class "Default")
      (node (ref "U23") (pin "M2") (pinfunction "~{SPIM_CS}_M2") (pintype "passive"))
      (node (ref "U24") (pin "1") (pinfunction "~{CS}_1") (pintype "passive"))
    )
    (net (code "41") (name "Net-(U24-~{HOLD})") (class "Default")
      (node (ref "R100") (pin "1") (pinfunction "1_1") (pintype "passive"))
      (node (ref "R96") (pin "1") (pinfunction "1_1") (pintype "passive"))
      (node (ref "U24") (pin "7") (pinfunction "~{HOLD}_7") (pintype "passive"))
    )
    (net (code "42") (name "Net-(U24-~{WP})") (class "Default")
      (node (ref "R101") (pin "1") (pinfunction "1_1") (pintype "passive"))
      (node (ref "R97") (pin "1") (pinfunction "1_1") (pintype "passive"))
      (node (ref "U24") (pin "3") (pinfunction "~{WP}_3") (pintype "passive"))
    )
    (net (code "43") (name "Net-(X13-I)") (class "Default")
      (node (ref "L22") (pin "2") (pinfunction "2_2") (pintype "passive"))
      (node (ref "L23") (pin "2") (pinfunction "2_2") (pintype "passive"))
      (node (ref "X13") (pin "1") (pinfunction "I_1") (pintype "passive"))
    )
    (net (code "44") (name "Net-(X13-O)") (class "Default")
      (node (ref "C156") (pin "1") (pinfunction "1_1") (pintype "passive"))
      (node (ref "X13") (pin "2") (pinfunction "O_2") (pintype "passive"))
    )
    (net (code "45") (name "unconnected-(U23-ANTC-PadL1)") (class "Default")
      (node (ref "U23") (pin "L1") (pinfunction "ANTC_L1") (pintype "output"))
    )
    (net (code "46") (name "unconnected-(U23-ANTD-PadT1)") (class "Default")
      (node (ref "U23") (pin "T1") (pinfunction "ANTD_T1") (pintype "output"))
    )
    (net (code "47") (name "unconnected-(U23-ANTE-PadT2)") (class "Default")
      (node (ref "U23") (pin "T2") (pinfunction "ANTE_T2") (pintype "output"))
    )
    (net (code "48") (name "unconnected-(U23-NC_A12-PadA12)") (class "Default")
      (node (ref "U23") (pin "A12") (pinfunction "NC_A12_A12") (pintype "passive"))
    )
    (net (code "49") (name "unconnected-(U23-NC_A13-PadA13)") (class "Default")
      (node (ref "U23") (pin "A13") (pinfunction "NC_A13_A13") (pintype "passive"))
    )
    (net (code "50") (name "unconnected-(U23-NC_A14-PadA14)") (class "Default")
      (node (ref "U23") (pin "A14") (pinfunction "NC_A14_A14") (pintype "passive"))
    )
    (net (code "51") (name "unconnected-(U23-NC_A15-PadA15)") (class "Default")
      (node (ref "U23") (pin "A15") (pinfunction "NC_A15_A15") (pintype "passive"))
    )
    (net (code "52") (name "unconnected-(U23-NC_A16-PadA16)") (class "Default")
      (node (ref "U23") (pin "A16") (pinfunction "NC_A16_A16") (pintype "passive"))
    )
    (net (code "53") (name "unconnected-(U23-NC_A17-PadA17)") (class "Default")
      (node (ref "U23") (pin "A17") (pinfunction "NC_A17_A17") (pintype "passive"))
    )
    (net (code "54") (name "unconnected-(U23-NC_B3-PadB3)") (class "Default")
      (node (ref "U23") (pin "B3") (pinfunction "NC_B3_B3") (pintype "passive"))
    )
    (net (code "55") (name "unconnected-(U23-NC_B12-PadB12)") (class "Default")
      (node (ref "U23") (pin "B12") (pinfunction "NC_B12_B12") (pintype "passive"))
    )
    (net (code "56") (name "unconnected-(U23-NC_B13-PadB13)") (class "Default")
      (node (ref "U23") (pin "B13") (pinfunction "NC_B13_B13") (pintype "passive"))
    )
    (net (code "57") (name "unconnected-(U23-NC_B14-PadB14)") (class "Default")
      (node (ref "U23") (pin "B14") (pinfunction "NC_B14_B14") (pintype "passive"))
    )
    (net (code "58") (name "unconnected-(U23-NC_B15-PadB15)") (class "Default")
      (node (ref "U23") (pin "B15") (pinfunction "NC_B15_B15") (pintype "passive"))
    )
    (net (code "59") (name "unconnected-(U23-NC_C2-PadC2)") (class "Default")
      (node (ref "U23") (pin "C2") (pinfunction "NC_C2_C2") (pintype "passive"))
    )
    (net (code "60") (name "unconnected-(U23-NC_C16-PadC16)") (class "Default")
      (node (ref "U23") (pin "C16") (pinfunction "NC_C16_C16") (pintype "passive"))
    )
    (net (code "61") (name "unconnected-(U23-NC_D2-PadD2)") (class "Default")
      (node (ref "U23") (pin "D2") (pinfunction "NC_D2_D2") (pintype "passive"))
    )
    (net (code "62") (name "unconnected-(U23-NC_D16-PadD16)") (class "Default")
      (node (ref "U23") (pin "D16") (pinfunction "NC_D16_D16") (pintype "passive"))
    )
    (net (code "63") (name "unconnected-(U23-NC_E2-PadE2)") (class "Default")
      (node (ref "U23") (pin "E2") (pinfunction "NC_E2_E2") (pintype "passive"))
    )
    (net (code "64") (name "unconnected-(U23-NC_E16-PadE16)") (class "Default")
      (node (ref "U23") (pin "E16") (pinfunction "NC_E16_E16") (pintype "passive"))
    )
    (net (code "65") (name "unconnected-(U23-NC_F2-PadF2)") (class "Default")
      (node (ref "U23") (pin "F2") (pinfunction "NC_F2_F2") (pintype "passive"))
    )
    (net (code "66") (name "unconnected-(U23-NC_F16-PadF16)") (class "Default")
      (node (ref "U23") (pin "F16") (pinfunction "NC_F16_F16") (pintype "passive"))
    )
    (net (code "67") (name "unconnected-(U23-NC_F17-PadF17)") (class "Default")
      (node (ref "U23") (pin "F17") (pinfunction "NC_F17_F17") (pintype "passive"))
    )
    (net (code "68") (name "unconnected-(U23-NC_G17-PadG17)") (class "Default")
      (node (ref "U23") (pin "G17") (pinfunction "NC_G17_G17") (pintype "passive"))
    )
    (net (code "69") (name "unconnected-(U23-NC_H16-PadH16)") (class "Default")
      (node (ref "U23") (pin "H16") (pinfunction "NC_H16_H16") (pintype "passive"))
    )
    (net (code "70") (name "unconnected-(U23-NC_H17-PadH17)") (class "Default")
      (node (ref "U23") (pin "H17") (pinfunction "NC_H17_H17") (pintype "passive"))
    )
    (net (code "71") (name "unconnected-(U23-NC_J16-PadJ16)") (class "Default")
      (node (ref "U23") (pin "J16") (pinfunction "NC_J16_J16") (pintype "passive"))
    )
    (net (code "72") (name "unconnected-(U23-NC_J17-PadJ17)") (class "Default")
      (node (ref "U23") (pin "J17") (pinfunction "NC_J17_J17") (pintype "passive"))
    )
    (net (code "73") (name "unconnected-(U23-NC_K17-PadK17)") (class "Default")
      (node (ref "U23") (pin "K17") (pinfunction "NC_K17_K17") (pintype "passive"))
    )
    (net (code "74") (name "unconnected-(U23-NC_L16-PadL16)") (class "Default")
      (node (ref "U23") (pin "L16") (pinfunction "NC_L16_L16") (pintype "passive"))
    )
    (net (code "75") (name "unconnected-(U23-NC_L17-PadL17)") (class "Default")
      (node (ref "U23") (pin "L17") (pinfunction "NC_L17_L17") (pintype "passive"))
    )
    (net (code "76") (name "unconnected-(U23-NC_M1-PadM1)") (class "Default")
      (node (ref "U23") (pin "M1") (pinfunction "NC_M1_M1") (pintype "passive"))
    )
    (net (code "77") (name "unconnected-(U23-NC_M16-PadM16)") (class "Default")
      (node (ref "U23") (pin "M16") (pinfunction "NC_M16_M16") (pintype "passive"))
    )
    (net (code "78") (name "unconnected-(U23-NC_M17-PadM17)") (class "Default")
      (node (ref "U23") (pin "M17") (pinfunction "NC_M17_M17") (pintype "passive"))
    )
    (net (code "79") (name "unconnected-(U23-NC_N1-PadN1)") (class "Default")
      (node (ref "U23") (pin "N1") (pinfunction "NC_N1_N1") (pintype "passive"))
    )
    (net (code "80") (name "unconnected-(U23-NC_N16-PadN16)") (class "Default")
      (node (ref "U23") (pin "N16") (pinfunction "NC_N16_N16") (pintype "passive"))
    )
    (net (code "81") (name "unconnected-(U23-NC_N17-PadN17)") (class "Default")
      (node (ref "U23") (pin "N17") (pinfunction "NC_N17_N17") (pintype "passive"))
    )
    (net (code "82") (name "unconnected-(U23-NC_P1-PadP1)") (class "Default")
      (node (ref "U23") (pin "P1") (pinfunction "NC_P1_P1") (pintype "passive"))
    )
    (net (code "83") (name "unconnected-(U23-NC_P16-PadP16)") (class "Default")
      (node (ref "U23") (pin "P16") (pinfunction "NC_P16_P16") (pintype "passive"))
    )
    (net (code "84") (name "unconnected-(U23-NC_P17-PadP17)") (class "Default")
      (node (ref "U23") (pin "P17") (pinfunction "NC_P17_P17") (pintype "passive"))
    )
    (net (code "85") (name "unconnected-(U23-NC_R1-PadR1)") (class "Default")
      (node (ref "U23") (pin "R1") (pinfunction "NC_R1_R1") (pintype "passive"))
    )
    (net (code "86") (name "unconnected-(U23-NC_R3-PadR3)") (class "Default")
      (node (ref "U23") (pin "R3") (pinfunction "NC_R3_R3") (pintype "passive"))
    )
    (net (code "87") (name "unconnected-(U23-NC_R4-PadR4)") (class "Default")
      (node (ref "U23") (pin "R4") (pinfunction "NC_R4_R4") (pintype "passive"))
    )
    (net (code "88") (name "unconnected-(U23-NC_R5-PadR5)") (class "Default")
      (node (ref "U23") (pin "R5") (pinfunction "NC_R5_R5") (pintype "passive"))
    )
    (net (code "89") (name "unconnected-(U23-NC_R6-PadR6)") (class "Default")
      (node (ref "U23") (pin "R6") (pinfunction "NC_R6_R6") (pintype "passive"))
    )
    (net (code "90") (name "unconnected-(U23-NC_R8-PadR8)") (class "Default")
      (node (ref "U23") (pin "R8") (pinfunction "NC_R8_R8") (pintype "passive"))
    )
    (net (code "91") (name "unconnected-(U23-NC_R10-PadR10)") (class "Default")
      (node (ref "U23") (pin "R10") (pinfunction "NC_R10_R10") (pintype "passive"))
    )
    (net (code "92") (name "unconnected-(U23-NC_R11-PadR11)") (class "Default")
      (node (ref "U23") (pin "R11") (pinfunction "NC_R11_R11") (pintype "passive"))
    )
    (net (code "93") (name "unconnected-(U23-NC_R12-PadR12)") (class "Default")
      (node (ref "U23") (pin "R12") (pinfunction "NC_R12_R12") (pintype "passive"))
    )
    (net (code "94") (name "unconnected-(U23-NC_R13-PadR13)") (class "Default")
      (node (ref "U23") (pin "R13") (pinfunction "NC_R13_R13") (pintype "passive"))
    )
    (net (code "95") (name "unconnected-(U23-NC_R14-PadR14)") (class "Default")
      (node (ref "U23") (pin "R14") (pinfunction "NC_R14_R14") (pintype "passive"))
    )
    (net (code "96") (name "unconnected-(U23-NC_R15-PadR15)") (class "Default")
      (node (ref "U23") (pin "R15") (pinfunction "NC_R15_R15") (pintype "passive"))
    )
    (net (code "97") (name "unconnected-(U23-NC_R16-PadR16)") (class "Default")
      (node (ref "U23") (pin "R16") (pinfunction "NC_R16_R16") (pintype "passive"))
    )
    (net (code "98") (name "unconnected-(U23-NC_T13-PadT13)") (class "Default")
      (node (ref "U23") (pin "T13") (pinfunction "NC_T13_T13") (pintype "passive"))
    )
    (net (code "99") (name "unconnected-(U23-NC_T15-PadT15)") (class "Default")
      (node (ref "U23") (pin "T15") (pinfunction "NC_T15_T15") (pintype "passive"))
    )
    (net (code "100") (name "unconnected-(U23-PM_ENABLE-PadB10)") (class "Default")
      (node (ref "U23") (pin "B10") (pinfunction "PM_ENABLE_B10") (pintype "passive"))
    )
    (net (code "101") (name "unconnected-(U23-PM_MODE-PadB9)") (class "Default")
      (node (ref "U23") (pin "B9") (pinfunction "PM_MODE_B9") (pintype "passive"))
    )
    (net (code "102") (name "unconnected-(U23-SREG_OUT-PadB11)") (class "Default")
      (node (ref "U23") (pin "B11") (pinfunction "SREG_OUT_B11") (pintype "power_in"))
    )
  )
)
